# bbpreamp.net
KiCad netlist of a schematic drawn in EAGLE
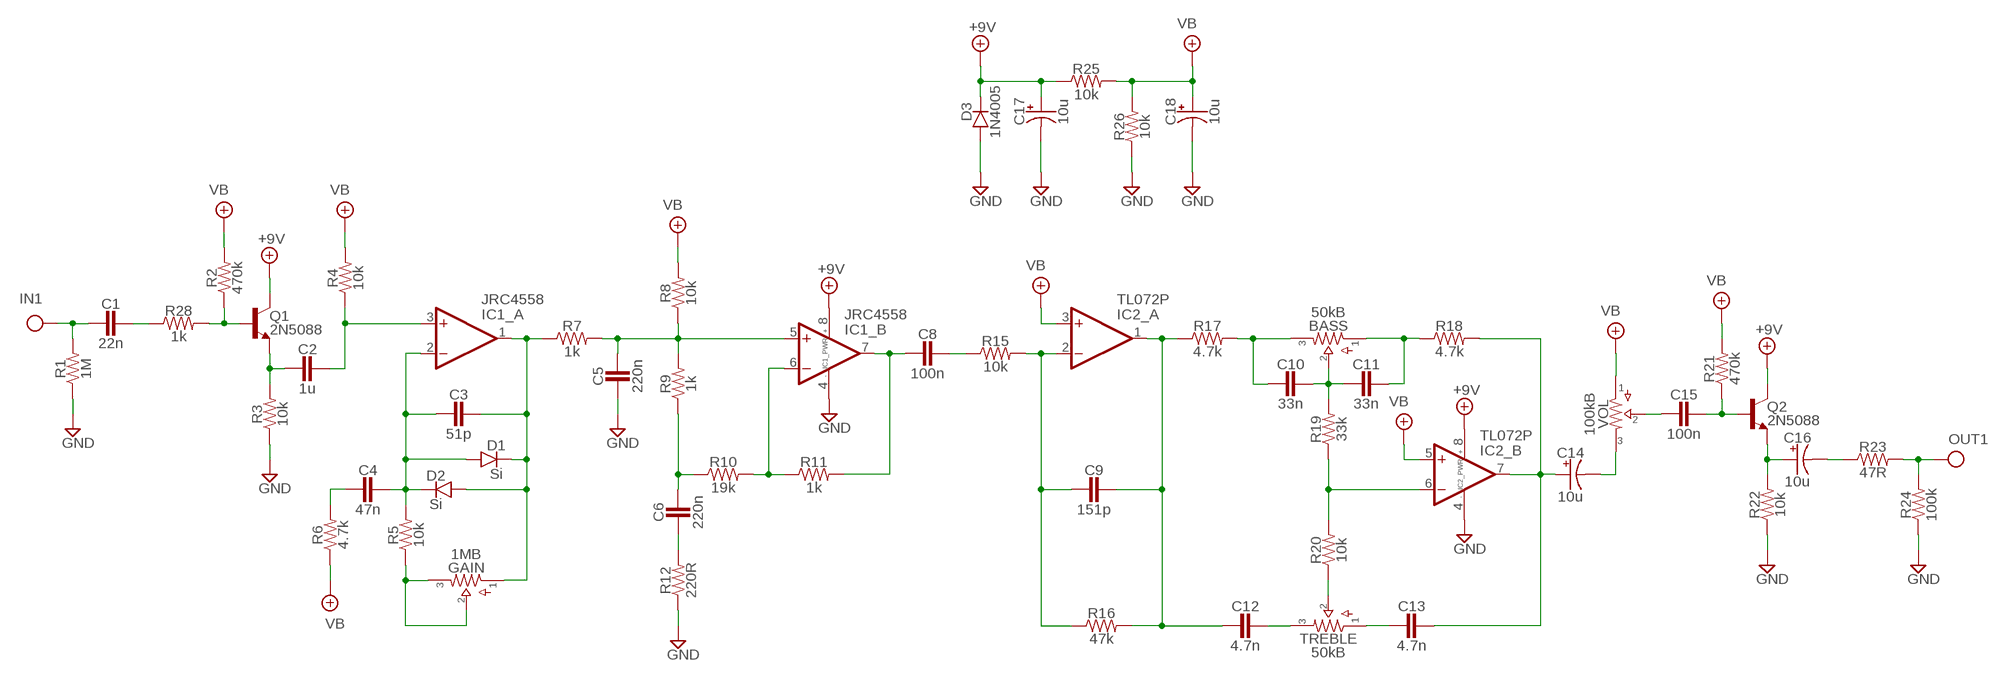
[diagram p0: schematic, sheet 1]

(export (version "E")
  (design (tool "Eeschema 10.0.6"))
  (components
    (comp (ref "BASS")
      (value "50kB")
      (footprint "eagle-import:16MM")
      (libsource (lib "eagle-import") (part "POTS16MM"))
    )
    (comp (ref "C1")
      (value "22n")
      (footprint "eagle-import:BOX_SMALL")
      (libsource (lib "eagle-import") (part "CER/FILMBOX.1"))
    )
    (comp (ref "C2")
      (value "1u")
      (footprint "eagle-import:BOX_SMALL")
      (libsource (lib "eagle-import") (part "CER/FILMBOX.1"))
    )
    (comp (ref "C3")
      (value "51p")
      (footprint "eagle-import:BOX_SMALL")
      (libsource (lib "eagle-import") (part "CER/FILMBOX.1"))
    )
    (comp (ref "C4")
      (value "47n")
      (footprint "eagle-import:BOX_SMALL")
      (libsource (lib "eagle-import") (part "CER/FILMBOX.1"))
    )
    (comp (ref "C5")
      (value "220n")
      (footprint "eagle-import:BOX_SMALL")
      (libsource (lib "eagle-import") (part "CER/FILMBOX.1"))
    )
    (comp (ref "C6")
      (value "220n")
      (footprint "eagle-import:BOX_SMALL")
      (libsource (lib "eagle-import") (part "CER/FILMBOX.1"))
    )
    (comp (ref "C8")
      (value "100n")
      (footprint "eagle-import:BOX_SMALL")
      (libsource (lib "eagle-import") (part "CER/FILMBOX.1"))
    )
    (comp (ref "C9")
      (value "151p")
      (footprint "eagle-import:BOX_SMALL")
      (libsource (lib "eagle-import") (part "CER/FILMBOX.1"))
    )
    (comp (ref "C10")
      (value "33n")
      (footprint "eagle-import:BOX_SMALL")
      (libsource (lib "eagle-import") (part "CER/FILMBOX.1"))
    )
    (comp (ref "C11")
      (value "33n")
      (footprint "eagle-import:BOX_SMALL")
      (libsource (lib "eagle-import") (part "CER/FILMBOX.1"))
    )
    (comp (ref "C12")
      (value "4.7n")
      (footprint "eagle-import:BOX_SMALL")
      (libsource (lib "eagle-import") (part "CER/FILMBOX.1"))
    )
    (comp (ref "C13")
      (value "4.7n")
      (footprint "eagle-import:BOX_SMALL")
      (libsource (lib "eagle-import") (part "CER/FILMBOX.1"))
    )
    (comp (ref "C14")
      (value "10u")
      (footprint "eagle-import:050_020")
      (libsource (lib "eagle-import") (part "0500"))
    )
    (comp (ref "C15")
      (value "100n")
      (footprint "eagle-import:BOX_SMALL")
      (libsource (lib "eagle-import") (part "CER/FILMBOX.1"))
    )
    (comp (ref "C16")
      (value "10u")
      (footprint "eagle-import:050_020")
      (libsource (lib "eagle-import") (part "0500"))
    )
    (comp (ref "C17")
      (value "10u")
      (footprint "eagle-import:050_020")
      (libsource (lib "eagle-import") (part "0500"))
    )
    (comp (ref "C18")
      (value "10u")
      (footprint "eagle-import:050_020")
      (libsource (lib "eagle-import") (part "0500"))
    )
    (comp (ref "D1")
      (value "Si")
      (footprint "eagle-import:DO35-2")
      (libsource (lib "eagle-import") (part "DO35.2"))
    )
    (comp (ref "D2")
      (value "Si")
      (footprint "eagle-import:DO35-2")
      (libsource (lib "eagle-import") (part "DO35.2"))
    )
    (comp (ref "D3")
      (value "1N4005")
      (footprint "eagle-import:DO41-3")
      (libsource (lib "eagle-import") (part "DO41.3"))
    )
    (comp (ref "GAIN")
      (value "1MB")
      (footprint "eagle-import:16MM")
      (libsource (lib "eagle-import") (part "POTS16MM"))
    )
    (comp (ref "IC1")
      (value "JRC4558")
      (footprint "eagle-import:DIL0")
      (libsource (lib "eagle-import") (part "DUALTH"))
    )
    (comp (ref "IC2")
      (value "TL072P")
      (footprint "eagle-import:DIL0")
      (libsource (lib "eagle-import") (part "DUALTH"))
    )
    (comp (ref "Q1")
      (value "2N5088")
      (footprint "eagle-import:TO92-")
      (libsource (lib "eagle-import") (part "2N5088"))
    )
    (comp (ref "Q2")
      (value "2N5088")
      (footprint "eagle-import:TO92-")
      (libsource (lib "eagle-import") (part "2N5088"))
    )
    (comp (ref "R1")
      (value "1M")
      (footprint "eagle-import:R0207_3")
      (libsource (lib "eagle-import") (part "R_.3B"))
    )
    (comp (ref "R2")
      (value "470k")
      (footprint "eagle-import:R0207_3")
      (libsource (lib "eagle-import") (part "R_.3B"))
    )
    (comp (ref "R3")
      (value "10k")
      (footprint "eagle-import:R0207_3")
      (libsource (lib "eagle-import") (part "R_.3B"))
    )
    (comp (ref "R4")
      (value "10k")
      (footprint "eagle-import:R0207_3")
      (libsource (lib "eagle-import") (part "R_.3B"))
    )
    (comp (ref "R5")
      (value "10k")
      (footprint "eagle-import:R0207_3")
      (libsource (lib "eagle-import") (part "R_.3B"))
    )
    (comp (ref "R6")
      (value "4.7k")
      (footprint "eagle-import:R0207_3")
      (libsource (lib "eagle-import") (part "R_.3B"))
    )
    (comp (ref "R7")
      (value "1k")
      (footprint "eagle-import:R0207_3")
      (libsource (lib "eagle-import") (part "R_.3B"))
    )
    (comp (ref "R8")
      (value "10k")
      (footprint "eagle-import:R0207_3")
      (libsource (lib "eagle-import") (part "R_.3B"))
    )
    (comp (ref "R9")
      (value "1k")
      (footprint "eagle-import:R0207_3")
      (libsource (lib "eagle-import") (part "R_.3B"))
    )
    (comp (ref "R10")
      (value "19k")
      (footprint "eagle-import:R0207_3")
      (libsource (lib "eagle-import") (part "R_.3B"))
    )
    (comp (ref "R11")
      (value "1k")
      (footprint "eagle-import:R0207_3")
      (libsource (lib "eagle-import") (part "R_.3B"))
    )
    (comp (ref "R12")
      (value "220R")
      (footprint "eagle-import:R0207_3")
      (libsource (lib "eagle-import") (part "R_.3B"))
    )
    (comp (ref "R15")
      (value "10k")
      (footprint "eagle-import:R0207_3")
      (libsource (lib "eagle-import") (part "R_.3B"))
    )
    (comp (ref "R16")
      (value "47k")
      (footprint "eagle-import:R0207_3")
      (libsource (lib "eagle-import") (part "R_.3B"))
    )
    (comp (ref "R17")
      (value "4.7k")
      (footprint "eagle-import:R0207_3")
      (libsource (lib "eagle-import") (part "R_.3B"))
    )
    (comp (ref "R18")
      (value "4.7k")
      (footprint "eagle-import:R0207_3")
      (libsource (lib "eagle-import") (part "R_.3B"))
    )
    (comp (ref "R19")
      (value "33k")
      (footprint "eagle-import:R0207_3")
      (libsource (lib "eagle-import") (part "R_.3B"))
    )
    (comp (ref "R20")
      (value "10k")
      (footprint "eagle-import:R0207_3")
      (libsource (lib "eagle-import") (part "R_.3B"))
    )
    (comp (ref "R21")
      (value "470k")
      (footprint "eagle-import:R0207_3")
      (libsource (lib "eagle-import") (part "R_.3B"))
    )
    (comp (ref "R22")
      (value "10k")
      (footprint "eagle-import:R0207_3")
      (libsource (lib "eagle-import") (part "R_.3B"))
    )
    (comp (ref "R23")
      (value "47R")
      (footprint "eagle-import:R0207_3")
      (libsource (lib "eagle-import") (part "R_.3B"))
    )
    (comp (ref "R24")
      (value "100k")
      (footprint "eagle-import:R0207_3")
      (libsource (lib "eagle-import") (part "R_.3B"))
    )
    (comp (ref "R25")
      (value "10k")
      (footprint "eagle-import:R0207_3")
      (libsource (lib "eagle-import") (part "R_.3B"))
    )
    (comp (ref "R26")
      (value "10k")
      (footprint "eagle-import:R0207_3")
      (libsource (lib "eagle-import") (part "R_.3B"))
    )
    (comp (ref "R28")
      (value "1k")
      (footprint "eagle-import:R0207_3")
      (libsource (lib "eagle-import") (part "R_.3B"))
    )
    (comp (ref "TREBLE")
      (value "50kB")
      (footprint "eagle-import:16MM")
      (libsource (lib "eagle-import") (part "POTS16MM"))
    )
    (comp (ref "VOL")
      (value "100kB")
      (footprint "eagle-import:16MM")
      (libsource (lib "eagle-import") (part "POTS16MM"))
    )
  )
  (nets
    (net (code "1") (name "+9V") (class "Default")
      (node (ref "C17") (pin "+") (pinfunction "+_+") (pintype "passive"))
      (node (ref "D3") (pin "C") (pinfunction "C_C") (pintype "passive"))
      (node (ref "IC1") (pin "8") (pinfunction "V+_8") (pintype "power_in"))
      (node (ref "IC2") (pin "8") (pinfunction "V+_8") (pintype "power_in"))
      (node (ref "Q1") (pin "1") (pinfunction "C_1") (pintype "passive"))
      (node (ref "Q2") (pin "1") (pinfunction "C_1") (pintype "passive"))
      (node (ref "R25") (pin "1") (pinfunction "1_1") (pintype "passive"))
    )
    (net (code "2") (name "GND") (class "Default")
      (node (ref "C17") (pin "-") (pinfunction "-_-") (pintype "passive"))
      (node (ref "C18") (pin "-") (pinfunction "-_-") (pintype "passive"))
      (node (ref "C5") (pin "2") (pinfunction "2_2") (pintype "passive"))
      (node (ref "D3") (pin "A") (pinfunction "A_A") (pintype "passive"))
      (node (ref "IC1") (pin "4") (pinfunction "V-_4") (pintype "power_in"))
      (node (ref "IC2") (pin "4") (pinfunction "V-_4") (pintype "power_in"))
      (node (ref "R1") (pin "1") (pinfunction "1_1") (pintype "passive"))
      (node (ref "R12") (pin "1") (pinfunction "1_1") (pintype "passive"))
      (node (ref "R22") (pin "1") (pinfunction "1_1") (pintype "passive"))
      (node (ref "R24") (pin "1") (pinfunction "1_1") (pintype "passive"))
      (node (ref "R26") (pin "1") (pinfunction "1_1") (pintype "passive"))
      (node (ref "R3") (pin "1") (pinfunction "1_1") (pintype "passive"))
    )
    (net (code "3") (name "IN") (class "Default")
      (node (ref "C1") (pin "2") (pinfunction "2_2") (pintype "passive"))
      (node (ref "R1") (pin "2") (pinfunction "2_2") (pintype "passive"))
    )
    (net (code "4") (name "Net-(BASS-Pad1)") (class "Default")
      (node (ref "BASS") (pin "1") (pinfunction "1_1") (pintype "passive"))
      (node (ref "C11") (pin "1") (pinfunction "1_1") (pintype "passive"))
      (node (ref "R18") (pin "1") (pinfunction "1_1") (pintype "passive"))
    )
    (net (code "5") (name "Net-(BASS-Pad2)") (class "Default")
      (node (ref "BASS") (pin "2") (pinfunction "2_2") (pintype "passive"))
      (node (ref "C10") (pin "1") (pinfunction "1_1") (pintype "passive"))
      (node (ref "C11") (pin "2") (pinfunction "2_2") (pintype "passive"))
      (node (ref "R19") (pin "2") (pinfunction "2_2") (pintype "passive"))
    )
    (net (code "6") (name "Net-(BASS-Pad3)") (class "Default")
      (node (ref "BASS") (pin "3") (pinfunction "3_3") (pintype "passive"))
      (node (ref "C10") (pin "2") (pinfunction "2_2") (pintype "passive"))
      (node (ref "R17") (pin "2") (pinfunction "2_2") (pintype "passive"))
    )
    (net (code "7") (name "Net-(C1-Pad1)") (class "Default")
      (node (ref "C1") (pin "1") (pinfunction "1_1") (pintype "passive"))
      (node (ref "R28") (pin "1") (pinfunction "1_1") (pintype "passive"))
    )
    (net (code "8") (name "Net-(C4-Pad2)") (class "Default")
      (node (ref "C4") (pin "2") (pinfunction "2_2") (pintype "passive"))
      (node (ref "R6") (pin "2") (pinfunction "2_2") (pintype "passive"))
    )
    (net (code "9") (name "Net-(C6-Pad1)") (class "Default")
      (node (ref "C6") (pin "1") (pinfunction "1_1") (pintype "passive"))
      (node (ref "R10") (pin "1") (pinfunction "1_1") (pintype "passive"))
      (node (ref "R9") (pin "1") (pinfunction "1_1") (pintype "passive"))
    )
    (net (code "10") (name "Net-(C6-Pad2)") (class "Default")
      (node (ref "C6") (pin "2") (pinfunction "2_2") (pintype "passive"))
      (node (ref "R12") (pin "2") (pinfunction "2_2") (pintype "passive"))
    )
    (net (code "11") (name "Net-(C8-Pad1)") (class "Default")
      (node (ref "C8") (pin "1") (pinfunction "1_1") (pintype "passive"))
      (node (ref "R15") (pin "1") (pinfunction "1_1") (pintype "passive"))
    )
    (net (code "12") (name "Net-(C12-Pad1)") (class "Default")
      (node (ref "C12") (pin "1") (pinfunction "1_1") (pintype "passive"))
      (node (ref "TREBLE") (pin "3") (pinfunction "3_3") (pintype "passive"))
    )
    (net (code "13") (name "Net-(C13-Pad2)") (class "Default")
      (node (ref "C13") (pin "2") (pinfunction "2_2") (pintype "passive"))
      (node (ref "TREBLE") (pin "1") (pinfunction "1_1") (pintype "passive"))
    )
    (net (code "14") (name "Net-(C14-Pad-)") (class "Default")
      (node (ref "C14") (pin "-") (pinfunction "-_-") (pintype "passive"))
      (node (ref "VOL") (pin "3") (pinfunction "3_3") (pintype "passive"))
    )
    (net (code "15") (name "Net-(C15-Pad2)") (class "Default")
      (node (ref "C15") (pin "2") (pinfunction "2_2") (pintype "passive"))
      (node (ref "VOL") (pin "2") (pinfunction "2_2") (pintype "passive"))
    )
    (net (code "16") (name "Net-(C16-Pad-)") (class "Default")
      (node (ref "C16") (pin "-") (pinfunction "-_-") (pintype "passive"))
      (node (ref "R23") (pin "1") (pinfunction "1_1") (pintype "passive"))
    )
    (net (code "17") (name "Net-(GAIN-Pad2)") (class "Default")
      (node (ref "GAIN") (pin "2") (pinfunction "2_2") (pintype "passive"))
      (node (ref "GAIN") (pin "3") (pinfunction "3_3") (pintype "passive"))
      (node (ref "R5") (pin "1") (pinfunction "1_1") (pintype "passive"))
    )
    (net (code "18") (name "Net-(IC1A-+IN)") (class "Default")
      (node (ref "C2") (pin "1") (pinfunction "1_1") (pintype "passive"))
      (node (ref "IC1") (pin "3") (pinfunction "+IN_3") (pintype "input"))
      (node (ref "R4") (pin "1") (pinfunction "1_1") (pintype "passive"))
    )
    (net (code "19") (name "Net-(IC1A--IN)") (class "Default")
      (node (ref "C3") (pin "2") (pinfunction "2_2") (pintype "passive"))
      (node (ref "C4") (pin "1") (pinfunction "1_1") (pintype "passive"))
      (node (ref "D1") (pin "A") (pinfunction "A_A") (pintype "passive"))
      (node (ref "D2") (pin "C") (pinfunction "C_C") (pintype "passive"))
      (node (ref "IC1") (pin "2") (pinfunction "-IN_2") (pintype "input"))
      (node (ref "R5") (pin "2") (pinfunction "2_2") (pintype "passive"))
    )
    (net (code "20") (name "Net-(IC1A-OUT)") (class "Default")
      (node (ref "C3") (pin "1") (pinfunction "1_1") (pintype "passive"))
      (node (ref "D1") (pin "C") (pinfunction "C_C") (pintype "passive"))
      (node (ref "D2") (pin "A") (pinfunction "A_A") (pintype "passive"))
      (node (ref "GAIN") (pin "1") (pinfunction "1_1") (pintype "passive"))
      (node (ref "IC1") (pin "1") (pinfunction "OUT_1") (pintype "output"))
      (node (ref "R7") (pin "1") (pinfunction "1_1") (pintype "passive"))
    )
    (net (code "21") (name "Net-(IC1B-+IN)") (class "Default")
      (node (ref "C5") (pin "1") (pinfunction "1_1") (pintype "passive"))
      (node (ref "IC1") (pin "5") (pinfunction "+IN_5") (pintype "input"))
      (node (ref "R7") (pin "2") (pinfunction "2_2") (pintype "passive"))
      (node (ref "R8") (pin "1") (pinfunction "1_1") (pintype "passive"))
      (node (ref "R9") (pin "2") (pinfunction "2_2") (pintype "passive"))
    )
    (net (code "22") (name "Net-(IC1B--IN)") (class "Default")
      (node (ref "IC1") (pin "6") (pinfunction "-IN_6") (pintype "input"))
      (node (ref "R10") (pin "2") (pinfunction "2_2") (pintype "passive"))
      (node (ref "R11") (pin "1") (pinfunction "1_1") (pintype "passive"))
    )
    (net (code "23") (name "Net-(IC1B-OUT)") (class "Default")
      (node (ref "C8") (pin "2") (pinfunction "2_2") (pintype "passive"))
      (node (ref "IC1") (pin "7") (pinfunction "OUT_7") (pintype "output"))
      (node (ref "R11") (pin "2") (pinfunction "2_2") (pintype "passive"))
    )
    (net (code "24") (name "Net-(IC2A--IN)") (class "Default")
      (node (ref "C9") (pin "2") (pinfunction "2_2") (pintype "passive"))
      (node (ref "IC2") (pin "2") (pinfunction "-IN_2") (pintype "input"))
      (node (ref "R15") (pin "2") (pinfunction "2_2") (pintype "passive"))
      (node (ref "R16") (pin "1") (pinfunction "1_1") (pintype "passive"))
    )
    (net (code "25") (name "Net-(IC2A-OUT)") (class "Default")
      (node (ref "C12") (pin "2") (pinfunction "2_2") (pintype "passive"))
      (node (ref "C9") (pin "1") (pinfunction "1_1") (pintype "passive"))
      (node (ref "IC2") (pin "1") (pinfunction "OUT_1") (pintype "output"))
      (node (ref "R16") (pin "2") (pinfunction "2_2") (pintype "passive"))
      (node (ref "R17") (pin "1") (pinfunction "1_1") (pintype "passive"))
    )
    (net (code "26") (name "Net-(IC2B--IN)") (class "Default")
      (node (ref "IC2") (pin "6") (pinfunction "-IN_6") (pintype "input"))
      (node (ref "R19") (pin "1") (pinfunction "1_1") (pintype "passive"))
      (node (ref "R20") (pin "2") (pinfunction "2_2") (pintype "passive"))
    )
    (net (code "27") (name "Net-(IC2B-OUT)") (class "Default")
      (node (ref "C13") (pin "1") (pinfunction "1_1") (pintype "passive"))
      (node (ref "C14") (pin "+") (pinfunction "+_+") (pintype "passive"))
      (node (ref "IC2") (pin "7") (pinfunction "OUT_7") (pintype "output"))
      (node (ref "R18") (pin "2") (pinfunction "2_2") (pintype "passive"))
    )
    (net (code "28") (name "Net-(Q1-B)") (class "Default")
      (node (ref "Q1") (pin "2") (pinfunction "B_2") (pintype "passive"))
      (node (ref "R2") (pin "1") (pinfunction "1_1") (pintype "passive"))
      (node (ref "R28") (pin "2") (pinfunction "2_2") (pintype "passive"))
    )
    (net (code "29") (name "Net-(Q1-E)") (class "Default")
      (node (ref "C2") (pin "2") (pinfunction "2_2") (pintype "passive"))
      (node (ref "Q1") (pin "3") (pinfunction "E_3") (pintype "passive"))
      (node (ref "R3") (pin "2") (pinfunction "2_2") (pintype "passive"))
    )
    (net (code "30") (name "Net-(Q2-B)") (class "Default")
      (node (ref "C15") (pin "1") (pinfunction "1_1") (pintype "passive"))
      (node (ref "Q2") (pin "2") (pinfunction "B_2") (pintype "passive"))
      (node (ref "R21") (pin "1") (pinfunction "1_1") (pintype "passive"))
    )
    (net (code "31") (name "Net-(Q2-E)") (class "Default")
      (node (ref "C16") (pin "+") (pinfunction "+_+") (pintype "passive"))
      (node (ref "Q2") (pin "3") (pinfunction "E_3") (pintype "passive"))
      (node (ref "R22") (pin "2") (pinfunction "2_2") (pintype "passive"))
    )
    (net (code "32") (name "Net-(R20-Pad1)") (class "Default")
      (node (ref "R20") (pin "1") (pinfunction "1_1") (pintype "passive"))
      (node (ref "TREBLE") (pin "2") (pinfunction "2_2") (pintype "passive"))
    )
    (net (code "33") (name "OUT") (class "Default")
      (node (ref "R23") (pin "2") (pinfunction "2_2") (pintype "passive"))
      (node (ref "R24") (pin "2") (pinfunction "2_2") (pintype "passive"))
    )
    (net (code "34") (name "VB") (class "Default")
      (node (ref "C18") (pin "+") (pinfunction "+_+") (pintype "passive"))
      (node (ref "IC2") (pin "3") (pinfunction "+IN_3") (pintype "input"))
      (node (ref "IC2") (pin "5") (pinfunction "+IN_5") (pintype "input"))
      (node (ref "R2") (pin "2") (pinfunction "2_2") (pintype "passive"))
      (node (ref "R21") (pin "2") (pinfunction "2_2") (pintype "passive"))
      (node (ref "R25") (pin "2") (pinfunction "2_2") (pintype "passive"))
      (node (ref "R26") (pin "2") (pinfunction "2_2") (pintype "passive"))
      (node (ref "R4") (pin "2") (pinfunction "2_2") (pintype "passive"))
      (node (ref "R6") (pin "1") (pinfunction "1_1") (pintype "passive"))
      (node (ref "R8") (pin "2") (pinfunction "2_2") (pintype "passive"))
      (node (ref "VOL") (pin "1") (pinfunction "1_1") (pintype "passive"))
    )
  )
)
